# V_2.net
KiCad netlist of a schematic drawn in Altium Designer
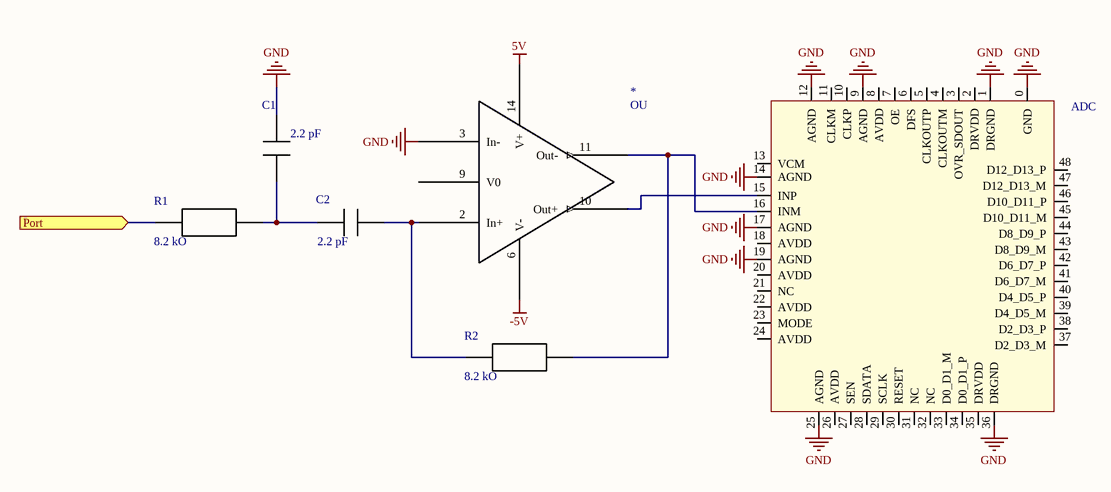
[diagram p0: V_2.SchDoc]

(export (version "E")
  (design (tool "Eeschema 10.0.6"))
  (components
    (comp (ref "*") (value "OU") (libsource (lib "V_2") (part "OU")))
    (comp (ref "ADC") (value "~") (libsource (lib "V_2") (part "ADC")))
    (comp (ref "C1") (value "2.2 pF") (libsource (lib "V_222") (part "Condens")))
    (comp (ref "C2") (value "2.2 pF") (libsource (lib "V_222") (part "Condens")))
    (comp (ref "R1") (value "8.2 kO") (libsource (lib "V_2") (part "Resist")))
    (comp (ref "R2") (value "8.2 kO") (libsource (lib "V_2") (part "Resist")))
  )
  (nets
    (net (code "1") (name "-5V") (class "Default")
      (node (ref "*") (pin "6") (pinfunction "V-_6") (pintype "passive"))
    )
    (net (code "4") (name "GND") (class "Default")
      (node (ref "*") (pin "3") (pinfunction "In-_3") (pintype "passive"))
      (node (ref "ADC") (pin "0") (pinfunction "GND_0") (pintype "passive"))
      (node (ref "ADC") (pin "1") (pinfunction "DRGND_1") (pintype "passive"))
      (node (ref "ADC") (pin "12") (pinfunction "AGND_12") (pintype "passive"))
      (node (ref "ADC") (pin "14") (pinfunction "AGND_14") (pintype "passive"))
      (node (ref "ADC") (pin "17") (pinfunction "AGND_17") (pintype "passive"))
      (node (ref "ADC") (pin "19") (pinfunction "AGND_19") (pintype "passive"))
      (node (ref "ADC") (pin "25") (pinfunction "AGND_25") (pintype "passive"))
      (node (ref "ADC") (pin "36") (pinfunction "DRGND_36") (pintype "passive"))
      (node (ref "ADC") (pin "9") (pinfunction "AGND_9") (pintype "passive"))
    )
    (net (code "5") (name "Net-(*-Out-)") (class "Default")
      (node (ref "*") (pin "11") (pinfunction "Out-_11") (pintype "output"))
      (node (ref "ADC") (pin "16") (pinfunction "INM_16") (pintype "passive"))
    )
    (net (code "6") (name "Net-(*-___Out+)") (class "Default")
      (node (ref "*") (pin "10") (pinfunction "___Out+_10") (pintype "output"))
      (node (ref "ADC") (pin "15") (pinfunction "INP_15") (pintype "passive"))
    )
    (net (code "7") (name "unconnected-(*-In+-Pad2)") (class "Default")
      (node (ref "*") (pin "2") (pinfunction "In+_2") (pintype "passive"))
    )
    (net (code "8") (name "unconnected-(*-V+-Pad14)") (class "Default")
      (node (ref "*") (pin "14") (pinfunction "V+_14") (pintype "passive"))
    )
    (net (code "9") (name "unconnected-(*-V0-Pad9)") (class "Default")
      (node (ref "*") (pin "9") (pinfunction "V0_9") (pintype "passive"))
    )
    (net (code "10") (name "unconnected-(ADC-AVDD-Pad8)") (class "Default")
      (node (ref "ADC") (pin "8") (pinfunction "AVDD_8") (pintype "passive"))
    )
    (net (code "11") (name "unconnected-(ADC-AVDD-Pad18)") (class "Default")
      (node (ref "ADC") (pin "18") (pinfunction "AVDD_18") (pintype "passive"))
    )
    (net (code "12") (name "unconnected-(ADC-AVDD-Pad20)") (class "Default")
      (node (ref "ADC") (pin "20") (pinfunction "AVDD_20") (pintype "passive"))
    )
    (net (code "13") (name "unconnected-(ADC-AVDD-Pad22)") (class "Default")
      (node (ref "ADC") (pin "22") (pinfunction "AVDD_22") (pintype "passive"))
    )
    (net (code "14") (name "unconnected-(ADC-AVDD-Pad24)") (class "Default")
      (node (ref "ADC") (pin "24") (pinfunction "AVDD_24") (pintype "passive"))
    )
    (net (code "15") (name "unconnected-(ADC-AVDD-Pad26)") (class "Default")
      (node (ref "ADC") (pin "26") (pinfunction "AVDD_26") (pintype "passive"))
    )
    (net (code "16") (name "unconnected-(ADC-CLKM-Pad11)") (class "Default")
      (node (ref "ADC") (pin "11") (pinfunction "CLKM_11") (pintype "passive"))
    )
    (net (code "17") (name "unconnected-(ADC-CLKOUTM-Pad4)") (class "Default")
      (node (ref "ADC") (pin "4") (pinfunction "CLKOUTM_4") (pintype "passive"))
    )
    (net (code "18") (name "unconnected-(ADC-CLKOUTP-Pad5)") (class "Default")
      (node (ref "ADC") (pin "5") (pinfunction "CLKOUTP_5") (pintype "passive"))
    )
    (net (code "19") (name "unconnected-(ADC-CLKP-Pad10)") (class "Default")
      (node (ref "ADC") (pin "10") (pinfunction "CLKP_10") (pintype "passive"))
    )
    (net (code "20") (name "unconnected-(ADC-D0_D1_M-Pad33)") (class "Default")
      (node (ref "ADC") (pin "33") (pinfunction "D0_D1_M_33") (pintype "passive"))
    )
    (net (code "21") (name "unconnected-(ADC-D0_D1_P-Pad34)") (class "Default")
      (node (ref "ADC") (pin "34") (pinfunction "D0_D1_P_34") (pintype "passive"))
    )
    (net (code "22") (name "unconnected-(ADC-D2_D3_M-Pad37)") (class "Default")
      (node (ref "ADC") (pin "37") (pinfunction "D2_D3_M_37") (pintype "passive"))
    )
    (net (code "23") (name "unconnected-(ADC-D2_D3_P-Pad38)") (class "Default")
      (node (ref "ADC") (pin "38") (pinfunction "D2_D3_P_38") (pintype "passive"))
    )
    (net (code "24") (name "unconnected-(ADC-D4_D5_M-Pad39)") (class "Default")
      (node (ref "ADC") (pin "39") (pinfunction "D4_D5_M_39") (pintype "passive"))
    )
    (net (code "25") (name "unconnected-(ADC-D4_D5_P-Pad40)") (class "Default")
      (node (ref "ADC") (pin "40") (pinfunction "D4_D5_P_40") (pintype "passive"))
    )
    (net (code "26") (name "unconnected-(ADC-D6_D7_M-Pad41)") (class "Default")
      (node (ref "ADC") (pin "41") (pinfunction "D6_D7_M_41") (pintype "passive"))
    )
    (net (code "27") (name "unconnected-(ADC-D6_D7_P-Pad42)") (class "Default")
      (node (ref "ADC") (pin "42") (pinfunction "D6_D7_P_42") (pintype "passive"))
    )
    (net (code "28") (name "unconnected-(ADC-D8_D9_M-Pad43)") (class "Default")
      (node (ref "ADC") (pin "43") (pinfunction "D8_D9_M_43") (pintype "passive"))
    )
    (net (code "29") (name "unconnected-(ADC-D8_D9_P-Pad44)") (class "Default")
      (node (ref "ADC") (pin "44") (pinfunction "D8_D9_P_44") (pintype "passive"))
    )
    (net (code "30") (name "unconnected-(ADC-D10_D11_M-Pad45)") (class "Default")
      (node (ref "ADC") (pin "45") (pinfunction "D10_D11_M_45") (pintype "passive"))
    )
    (net (code "31") (name "unconnected-(ADC-D10_D11_P-Pad46)") (class "Default")
      (node (ref "ADC") (pin "46") (pinfunction "D10_D11_P_46") (pintype "passive"))
    )
    (net (code "32") (name "unconnected-(ADC-D12_D13_M-Pad47)") (class "Default")
      (node (ref "ADC") (pin "47") (pinfunction "D12_D13_M_47") (pintype "passive"))
    )
    (net (code "33") (name "unconnected-(ADC-D12_D13_P-Pad48)") (class "Default")
      (node (ref "ADC") (pin "48") (pinfunction "D12_D13_P_48") (pintype "passive"))
    )
    (net (code "34") (name "unconnected-(ADC-DFS-Pad6)") (class "Default")
      (node (ref "ADC") (pin "6") (pinfunction "DFS_6") (pintype "passive"))
    )
    (net (code "35") (name "unconnected-(ADC-DRVDD-Pad2)") (class "Default")
      (node (ref "ADC") (pin "2") (pinfunction "DRVDD_2") (pintype "passive"))
    )
    (net (code "36") (name "unconnected-(ADC-DRVDD-Pad35)") (class "Default")
      (node (ref "ADC") (pin "35") (pinfunction "DRVDD_35") (pintype "passive"))
    )
    (net (code "37") (name "unconnected-(ADC-MODE-Pad23)") (class "Default")
      (node (ref "ADC") (pin "23") (pinfunction "MODE_23") (pintype "passive"))
    )
    (net (code "38") (name "unconnected-(ADC-NC-Pad21)") (class "Default")
      (node (ref "ADC") (pin "21") (pinfunction "NC_21") (pintype "passive"))
    )
    (net (code "39") (name "unconnected-(ADC-NC-Pad31)") (class "Default")
      (node (ref "ADC") (pin "31") (pinfunction "NC_31") (pintype "passive"))
    )
    (net (code "40") (name "unconnected-(ADC-NC-Pad32)") (class "Default")
      (node (ref "ADC") (pin "32") (pinfunction "NC_32") (pintype "passive"))
    )
    (net (code "41") (name "unconnected-(ADC-OE-Pad7)") (class "Default")
      (node (ref "ADC") (pin "7") (pinfunction "OE_7") (pintype "passive"))
    )
    (net (code "42") (name "unconnected-(ADC-OVR_SDOUT-Pad3)") (class "Default")
      (node (ref "ADC") (pin "3") (pinfunction "OVR_SDOUT_3") (pintype "passive"))
    )
    (net (code "43") (name "unconnected-(ADC-RESET-Pad30)") (class "Default")
      (node (ref "ADC") (pin "30") (pinfunction "RESET_30") (pintype "passive"))
    )
    (net (code "44") (name "unconnected-(ADC-SCLK-Pad29)") (class "Default")
      (node (ref "ADC") (pin "29") (pinfunction "SCLK_29") (pintype "passive"))
    )
    (net (code "45") (name "unconnected-(ADC-SDATA-Pad28)") (class "Default")
      (node (ref "ADC") (pin "28") (pinfunction "SDATA_28") (pintype "passive"))
    )
    (net (code "46") (name "unconnected-(ADC-SEN-Pad27)") (class "Default")
      (node (ref "ADC") (pin "27") (pinfunction "SEN_27") (pintype "passive"))
    )
    (net (code "47") (name "unconnected-(ADC-VCM-Pad13)") (class "Default")
      (node (ref "ADC") (pin "13") (pinfunction "VCM_13") (pintype "passive"))
    )
  )
)
